# SRAM_Breakout.net
KiCad netlist of a schematic drawn in EAGLE
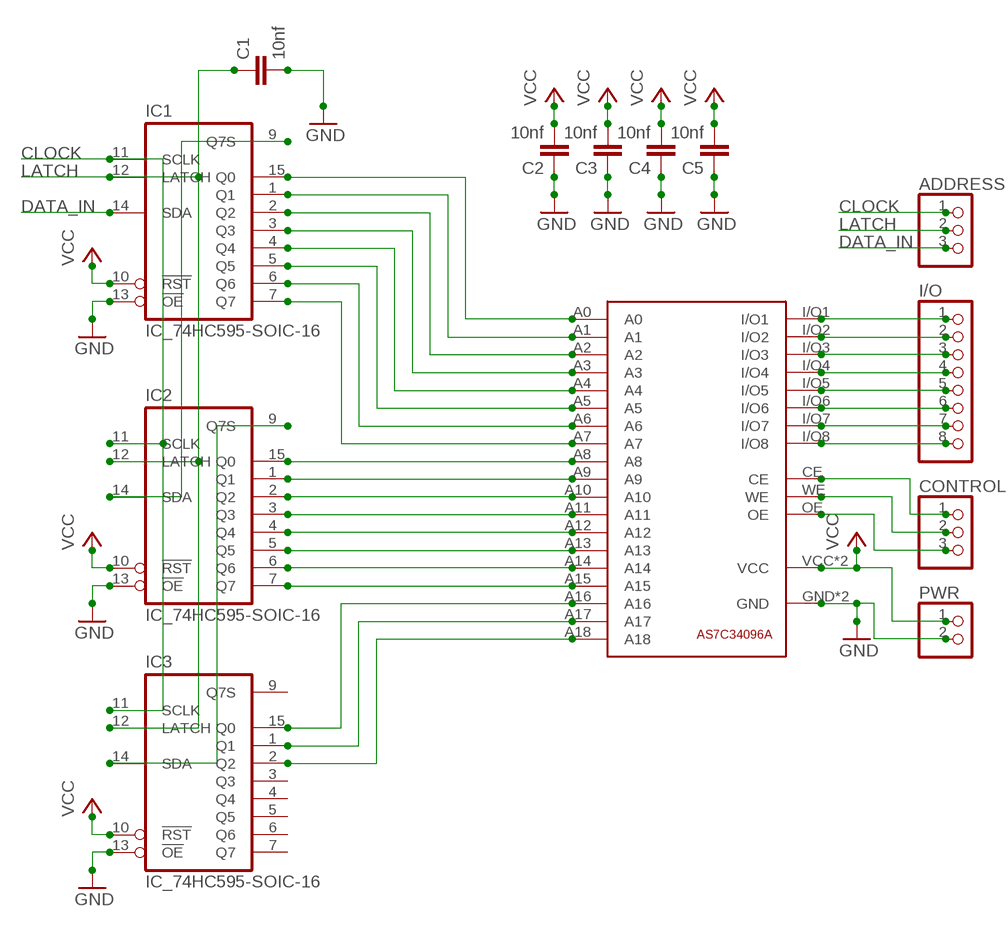
[diagram p0: schematic, sheet 1]

(export (version "E")
  (design (tool "Eeschema 10.0.6"))
  (components
    (comp (ref "ADDRESS")
      (value "PINHD-1X3/90")
      (footprint "eagle-import:1X03_90")
      (libsource (lib "eagle-import") (part "PINHD-1X3/90"))
    )
    (comp (ref "C1")
      (value "10nf")
      (footprint "eagle-import:C0603")
      (libsource (lib "eagle-import") (part "C-EUC0603"))
    )
    (comp (ref "C2")
      (value "10nf")
      (footprint "eagle-import:C0603")
      (libsource (lib "eagle-import") (part "C-EUC0603"))
    )
    (comp (ref "C3")
      (value "10nf")
      (footprint "eagle-import:C0603")
      (libsource (lib "eagle-import") (part "C-EUC0603"))
    )
    (comp (ref "C4")
      (value "10nf")
      (footprint "eagle-import:C0603")
      (libsource (lib "eagle-import") (part "C-EUC0603"))
    )
    (comp (ref "C5")
      (value "10nf")
      (footprint "eagle-import:C0603")
      (libsource (lib "eagle-import") (part "C-EUC0603"))
    )
    (comp (ref "CONTROL")
      (value "PINHD-1X3/90")
      (footprint "eagle-import:1X03_90")
      (libsource (lib "eagle-import") (part "PINHD-1X3/90"))
    )
    (comp (ref "I/O")
      (value "PINHD-1X8/90")
      (footprint "eagle-import:1X08_90")
      (libsource (lib "eagle-import") (part "PINHD-1X8/90"))
    )
    (comp (ref "IC1")
      (value "IC_74HC595-SOIC-16")
      (footprint "eagle-import:SOIC-16")
      (libsource (lib "eagle-import") (part "IC_74HC595-SOIC-16"))
    )
    (comp (ref "IC2")
      (value "IC_74HC595-SOIC-16")
      (footprint "eagle-import:SOIC-16")
      (libsource (lib "eagle-import") (part "IC_74HC595-SOIC-16"))
    )
    (comp (ref "IC3")
      (value "IC_74HC595-SOIC-16")
      (footprint "eagle-import:SOIC-16")
      (libsource (lib "eagle-import") (part "IC_74HC595-SOIC-16"))
    )
    (comp (ref "PWR")
      (value "PINHD-1X2/90")
      (footprint "eagle-import:1X02_90")
      (libsource (lib "eagle-import") (part "PINHD-1X2/90"))
    )
    (comp (ref "U$1")
      (value "AS7C34096A")
      (footprint "eagle-import:AS7C34096A")
      (libsource (lib "eagle-import") (part "AS7C34096A"))
    )
  )
  (nets
    (net (code "1") (name "/CLOCK") (class "Default")
      (node (ref "ADDRESS") (pin "1") (pinfunction "1_1") (pintype "passive"))
      (node (ref "IC1") (pin "11") (pinfunction "SCLK_11") (pintype "input"))
      (node (ref "IC2") (pin "11") (pinfunction "SCLK_11") (pintype "input"))
      (node (ref "IC3") (pin "11") (pinfunction "SCLK_11") (pintype "input"))
    )
    (net (code "2") (name "/DATA_IN") (class "Default")
      (node (ref "ADDRESS") (pin "3") (pinfunction "3_3") (pintype "passive"))
      (node (ref "IC1") (pin "14") (pinfunction "SDA_14") (pintype "input"))
    )
    (net (code "3") (name "/LATCH") (class "Default")
      (node (ref "ADDRESS") (pin "2") (pinfunction "2_2") (pintype "passive"))
      (node (ref "C1") (pin "1") (pinfunction "1_1") (pintype "passive"))
      (node (ref "IC1") (pin "12") (pinfunction "LATCH_12") (pintype "input"))
      (node (ref "IC2") (pin "12") (pinfunction "LATCH_12") (pintype "input"))
      (node (ref "IC3") (pin "12") (pinfunction "LATCH_12") (pintype "input"))
    )
    (net (code "4") (name "GND") (class "Default")
      (node (ref "C1") (pin "2") (pinfunction "2_2") (pintype "passive"))
      (node (ref "C2") (pin "1") (pinfunction "1_1") (pintype "passive"))
      (node (ref "C3") (pin "1") (pinfunction "1_1") (pintype "passive"))
      (node (ref "C4") (pin "1") (pinfunction "1_1") (pintype "passive"))
      (node (ref "C5") (pin "1") (pinfunction "1_1") (pintype "passive"))
      (node (ref "IC1") (pin "13") (pinfunction "~{OE}_13") (pintype "input"))
      (node (ref "IC2") (pin "13") (pinfunction "~{OE}_13") (pintype "input"))
      (node (ref "IC3") (pin "13") (pinfunction "~{OE}_13") (pintype "input"))
      (node (ref "PWR") (pin "2") (pinfunction "2_2") (pintype "passive"))
      (node (ref "U$1") (pin "GND") (pinfunction "GND_GND") (pintype "bidirectional"))
      (node (ref "U$1") (pin "GND0") (pinfunction "GND_GND0") (pintype "bidirectional"))
    )
    (net (code "5") (name "Net-(CONTROL-Pad1)") (class "Default")
      (node (ref "CONTROL") (pin "1") (pinfunction "1_1") (pintype "passive"))
      (node (ref "U$1") (pin "CE") (pinfunction "CE_CE") (pintype "bidirectional"))
    )
    (net (code "6") (name "Net-(CONTROL-Pad2)") (class "Default")
      (node (ref "CONTROL") (pin "2") (pinfunction "2_2") (pintype "passive"))
      (node (ref "U$1") (pin "WE") (pinfunction "WE_WE") (pintype "bidirectional"))
    )
    (net (code "7") (name "Net-(CONTROL-Pad3)") (class "Default")
      (node (ref "CONTROL") (pin "3") (pinfunction "3_3") (pintype "passive"))
      (node (ref "U$1") (pin "OE") (pinfunction "OE_OE") (pintype "bidirectional"))
    )
    (net (code "8") (name "Net-(I/O-Pad1)") (class "Default")
      (node (ref "I/O") (pin "1") (pinfunction "1_1") (pintype "passive"))
      (node (ref "U$1") (pin "I/O1") (pinfunction "I/O1_I/O1") (pintype "bidirectional"))
    )
    (net (code "9") (name "Net-(I/O-Pad2)") (class "Default")
      (node (ref "I/O") (pin "2") (pinfunction "2_2") (pintype "passive"))
      (node (ref "U$1") (pin "I/O2") (pinfunction "I/O2_I/O2") (pintype "bidirectional"))
    )
    (net (code "10") (name "Net-(I/O-Pad3)") (class "Default")
      (node (ref "I/O") (pin "3") (pinfunction "3_3") (pintype "passive"))
      (node (ref "U$1") (pin "I/O3") (pinfunction "I/O3_I/O3") (pintype "bidirectional"))
    )
    (net (code "11") (name "Net-(I/O-Pad4)") (class "Default")
      (node (ref "I/O") (pin "4") (pinfunction "4_4") (pintype "passive"))
      (node (ref "U$1") (pin "I/O4") (pinfunction "I/O4_I/O4") (pintype "bidirectional"))
    )
    (net (code "12") (name "Net-(I/O-Pad5)") (class "Default")
      (node (ref "I/O") (pin "5") (pinfunction "5_5") (pintype "passive"))
      (node (ref "U$1") (pin "I/O5") (pinfunction "I/O5_I/O5") (pintype "bidirectional"))
    )
    (net (code "13") (name "Net-(I/O-Pad6)") (class "Default")
      (node (ref "I/O") (pin "6") (pinfunction "6_6") (pintype "passive"))
      (node (ref "U$1") (pin "I/O6") (pinfunction "I/O6_I/O6") (pintype "bidirectional"))
    )
    (net (code "14") (name "Net-(I/O-Pad7)") (class "Default")
      (node (ref "I/O") (pin "7") (pinfunction "7_7") (pintype "passive"))
      (node (ref "U$1") (pin "I/O7") (pinfunction "I/O7_I/O7") (pintype "bidirectional"))
    )
    (net (code "15") (name "Net-(I/O-Pad8)") (class "Default")
      (node (ref "I/O") (pin "8") (pinfunction "8_8") (pintype "passive"))
      (node (ref "U$1") (pin "I/O8") (pinfunction "I/O8_I/O8") (pintype "bidirectional"))
    )
    (net (code "16") (name "Net-(IC1A-Q0)") (class "Default")
      (node (ref "IC1") (pin "15") (pinfunction "Q0_15") (pintype "output"))
      (node (ref "U$1") (pin "A0") (pinfunction "A0_A0") (pintype "bidirectional"))
    )
    (net (code "17") (name "Net-(IC1A-Q1)") (class "Default")
      (node (ref "IC1") (pin "1") (pinfunction "Q1_1") (pintype "output"))
      (node (ref "U$1") (pin "A1") (pinfunction "A1_A1") (pintype "bidirectional"))
    )
    (net (code "18") (name "Net-(IC1A-Q2)") (class "Default")
      (node (ref "IC1") (pin "2") (pinfunction "Q2_2") (pintype "output"))
      (node (ref "U$1") (pin "A2") (pinfunction "A2_A2") (pintype "bidirectional"))
    )
    (net (code "19") (name "Net-(IC1A-Q3)") (class "Default")
      (node (ref "IC1") (pin "3") (pinfunction "Q3_3") (pintype "output"))
      (node (ref "U$1") (pin "A3") (pinfunction "A3_A3") (pintype "bidirectional"))
    )
    (net (code "20") (name "Net-(IC1A-Q4)") (class "Default")
      (node (ref "IC1") (pin "4") (pinfunction "Q4_4") (pintype "output"))
      (node (ref "U$1") (pin "A4") (pinfunction "A4_A4") (pintype "bidirectional"))
    )
    (net (code "21") (name "Net-(IC1A-Q5)") (class "Default")
      (node (ref "IC1") (pin "5") (pinfunction "Q5_5") (pintype "output"))
      (node (ref "U$1") (pin "A5") (pinfunction "A5_A5") (pintype "bidirectional"))
    )
    (net (code "22") (name "Net-(IC1A-Q6)") (class "Default")
      (node (ref "IC1") (pin "6") (pinfunction "Q6_6") (pintype "output"))
      (node (ref "U$1") (pin "A6") (pinfunction "A6_A6") (pintype "bidirectional"))
    )
    (net (code "23") (name "Net-(IC1A-Q7)") (class "Default")
      (node (ref "IC1") (pin "7") (pinfunction "Q7_7") (pintype "output"))
      (node (ref "U$1") (pin "A7") (pinfunction "A7_A7") (pintype "bidirectional"))
    )
    (net (code "24") (name "Net-(IC1A-Q7S)") (class "Default")
      (node (ref "IC1") (pin "9") (pinfunction "Q7S_9") (pintype "output"))
      (node (ref "IC2") (pin "14") (pinfunction "SDA_14") (pintype "input"))
    )
    (net (code "25") (name "Net-(IC2A-Q0)") (class "Default")
      (node (ref "IC2") (pin "15") (pinfunction "Q0_15") (pintype "output"))
      (node (ref "U$1") (pin "A8") (pinfunction "A8_A8") (pintype "bidirectional"))
    )
    (net (code "26") (name "Net-(IC2A-Q1)") (class "Default")
      (node (ref "IC2") (pin "1") (pinfunction "Q1_1") (pintype "output"))
      (node (ref "U$1") (pin "A9") (pinfunction "A9_A9") (pintype "bidirectional"))
    )
    (net (code "27") (name "Net-(IC2A-Q2)") (class "Default")
      (node (ref "IC2") (pin "2") (pinfunction "Q2_2") (pintype "output"))
      (node (ref "U$1") (pin "A10") (pinfunction "A10_A10") (pintype "bidirectional"))
    )
    (net (code "28") (name "Net-(IC2A-Q3)") (class "Default")
      (node (ref "IC2") (pin "3") (pinfunction "Q3_3") (pintype "output"))
      (node (ref "U$1") (pin "A11") (pinfunction "A11_A11") (pintype "bidirectional"))
    )
    (net (code "29") (name "Net-(IC2A-Q4)") (class "Default")
      (node (ref "IC2") (pin "4") (pinfunction "Q4_4") (pintype "output"))
      (node (ref "U$1") (pin "A12") (pinfunction "A12_A12") (pintype "bidirectional"))
    )
    (net (code "30") (name "Net-(IC2A-Q5)") (class "Default")
      (node (ref "IC2") (pin "5") (pinfunction "Q5_5") (pintype "output"))
      (node (ref "U$1") (pin "A13") (pinfunction "A13_A13") (pintype "bidirectional"))
    )
    (net (code "31") (name "Net-(IC2A-Q6)") (class "Default")
      (node (ref "IC2") (pin "6") (pinfunction "Q6_6") (pintype "output"))
      (node (ref "U$1") (pin "A14") (pinfunction "A14_A14") (pintype "bidirectional"))
    )
    (net (code "32") (name "Net-(IC2A-Q7)") (class "Default")
      (node (ref "IC2") (pin "7") (pinfunction "Q7_7") (pintype "output"))
      (node (ref "U$1") (pin "A15") (pinfunction "A15_A15") (pintype "bidirectional"))
    )
    (net (code "33") (name "Net-(IC2A-Q7S)") (class "Default")
      (node (ref "IC2") (pin "9") (pinfunction "Q7S_9") (pintype "output"))
      (node (ref "IC3") (pin "14") (pinfunction "SDA_14") (pintype "input"))
    )
    (net (code "34") (name "Net-(IC3A-Q0)") (class "Default")
      (node (ref "IC3") (pin "15") (pinfunction "Q0_15") (pintype "output"))
      (node (ref "U$1") (pin "A16") (pinfunction "A16_A16") (pintype "bidirectional"))
    )
    (net (code "35") (name "Net-(IC3A-Q1)") (class "Default")
      (node (ref "IC3") (pin "1") (pinfunction "Q1_1") (pintype "output"))
      (node (ref "U$1") (pin "A17") (pinfunction "A17_A17") (pintype "bidirectional"))
    )
    (net (code "36") (name "Net-(IC3A-Q2)") (class "Default")
      (node (ref "IC3") (pin "2") (pinfunction "Q2_2") (pintype "output"))
      (node (ref "U$1") (pin "A18") (pinfunction "A18_A18") (pintype "bidirectional"))
    )
    (net (code "37") (name "VCC") (class "Default")
      (node (ref "C2") (pin "2") (pinfunction "2_2") (pintype "passive"))
      (node (ref "C3") (pin "2") (pinfunction "2_2") (pintype "passive"))
      (node (ref "C4") (pin "2") (pinfunction "2_2") (pintype "passive"))
      (node (ref "C5") (pin "2") (pinfunction "2_2") (pintype "passive"))
      (node (ref "IC1") (pin "10") (pinfunction "~{RST}_10") (pintype "input"))
      (node (ref "IC2") (pin "10") (pinfunction "~{RST}_10") (pintype "input"))
      (node (ref "IC3") (pin "10") (pinfunction "~{RST}_10") (pintype "input"))
      (node (ref "PWR") (pin "1") (pinfunction "1_1") (pintype "passive"))
      (node (ref "U$1") (pin "VCC") (pinfunction "VCC_VCC") (pintype "bidirectional"))
      (node (ref "U$1") (pin "VCC0") (pinfunction "VCC_VCC0") (pintype "bidirectional"))
    )
    (net (code "38") (name "unconnected-(IC3A-Q3-Pad3)") (class "Default")
      (node (ref "IC3") (pin "3") (pinfunction "Q3_3") (pintype "output"))
    )
    (net (code "39") (name "unconnected-(IC3A-Q4-Pad4)") (class "Default")
      (node (ref "IC3") (pin "4") (pinfunction "Q4_4") (pintype "output"))
    )
    (net (code "40") (name "unconnected-(IC3A-Q5-Pad5)") (class "Default")
      (node (ref "IC3") (pin "5") (pinfunction "Q5_5") (pintype "output"))
    )
    (net (code "41") (name "unconnected-(IC3A-Q6-Pad6)") (class "Default")
      (node (ref "IC3") (pin "6") (pinfunction "Q6_6") (pintype "output"))
    )
    (net (code "42") (name "unconnected-(IC3A-Q7-Pad7)") (class "Default")
      (node (ref "IC3") (pin "7") (pinfunction "Q7_7") (pintype "output"))
    )
    (net (code "43") (name "unconnected-(IC3A-Q7S-Pad9)") (class "Default")
      (node (ref "IC3") (pin "9") (pinfunction "Q7S_9") (pintype "output"))
    )
  )
)
